# power_aug_25.net
KiCad netlist of a schematic drawn in EAGLE
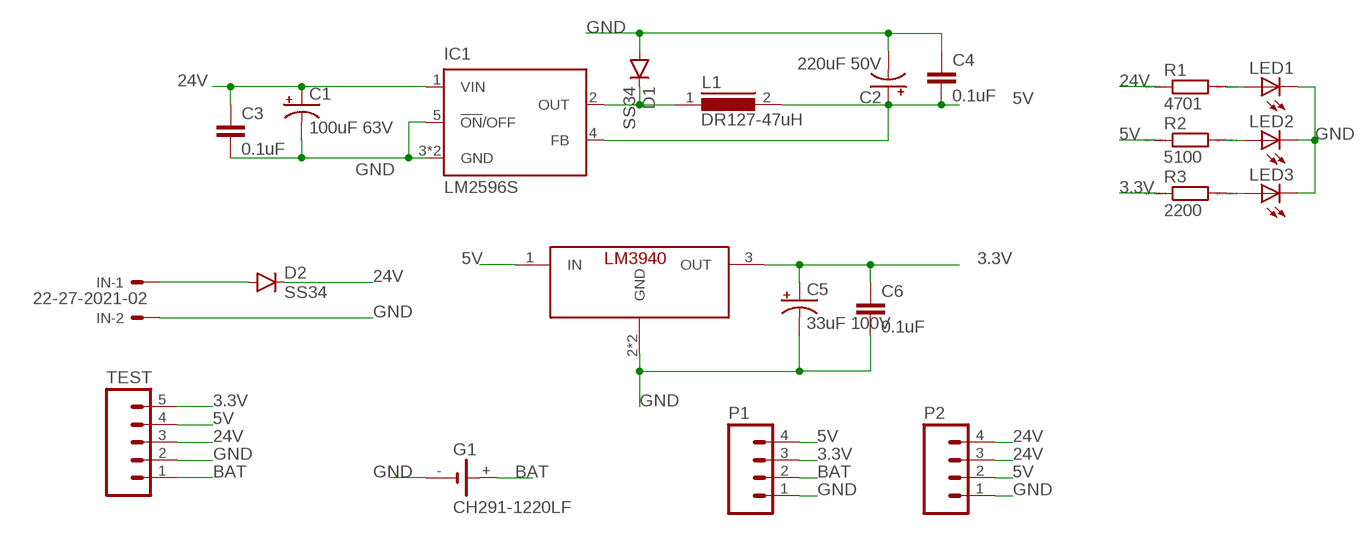
[diagram p0: schematic, sheet 1]

(export (version "E")
  (design (tool "Eeschema 10.0.6"))
  (components
    (comp (ref "C1")
      (value "100uF 63V")
      (footprint "eagle-import:NIC_10X10.5_CAP")
      (libsource (lib "eagle-import") (part "100UF-63V-20%(ELECT)"))
    )
    (comp (ref "C2")
      (value "220uF 50V")
      (footprint "eagle-import:NIC_10X10.5_CAP")
      (libsource (lib "eagle-import") (part "100UF-63V-20%(ELECT)"))
    )
    (comp (ref "C3")
      (value "0.1uF")
      (footprint "eagle-import:0603-CAP")
      (libsource (lib "eagle-import") (part "0.1UF-100V-10%(0603)"))
    )
    (comp (ref "C4")
      (value "0.1uF")
      (footprint "eagle-import:0603-CAP")
      (libsource (lib "eagle-import") (part "0.1UF-100V-10%(0603)"))
    )
    (comp (ref "C5")
      (value "33uF 100V")
      (footprint "eagle-import:NIC_10X10.5_CAP")
      (libsource (lib "eagle-import") (part "100UF-63V-20%(ELECT)"))
    )
    (comp (ref "C6")
      (value "0.1uF")
      (footprint "eagle-import:0603-CAP")
      (libsource (lib "eagle-import") (part "0.1UF-100V-10%(0603)"))
    )
    (comp (ref "D1")
      (value "SS34")
      (footprint "eagle-import:SMA-DIODE_ALT")
      (libsource (lib "eagle-import") (part "DIODESMA-ALT"))
    )
    (comp (ref "D2")
      (value "SS34")
      (footprint "eagle-import:SMA-DIODE_ALT")
      (libsource (lib "eagle-import") (part "DIODESMA-ALT"))
    )
    (comp (ref "G1")
      (value "CH291-1220LF")
      (footprint "eagle-import:CH291-1220LF")
      (libsource (lib "eagle-import") (part "CH291-1220LF"))
    )
    (comp (ref "IC1")
      (value "LM2596S")
      (footprint "eagle-import:TO263-5")
      (fields (field (name "MF") "NATIONAL SEMICONDUCTOR") (field (name "MPN") "LM2596S-ADJ/NOPB"))
      (libsource (lib "eagle-import") (part "LM2596S"))
    )
    (comp (ref "IN")
      (value "22-27-2021-02")
      (footprint "eagle-import:6410-02")
      (libsource (lib "eagle-import") (part "22-?-0227-2021"))
    )
    (comp (ref "L1")
      (value "DR127-47uH")
      (footprint "eagle-import:DR127")
      (libsource (lib "eagle-import") (part "DR127"))
    )
    (comp (ref "LED1")
      (value "LEDCHIPLED_0805")
      (footprint "eagle-import:CHIPLED_0805")
      (libsource (lib "eagle-import") (part "LEDCHIPLED_0805"))
    )
    (comp (ref "LED2")
      (value "LEDCHIPLED_0805")
      (footprint "eagle-import:CHIPLED_0805")
      (libsource (lib "eagle-import") (part "LEDCHIPLED_0805"))
    )
    (comp (ref "LED3")
      (value "LEDCHIPLED_0805")
      (footprint "eagle-import:CHIPLED_0805")
      (libsource (lib "eagle-import") (part "LEDCHIPLED_0805"))
    )
    (comp (ref "P1")
      (value "M04SMD2")
      (footprint "eagle-import:1X04-1MM-RA")
      (libsource (lib "eagle-import") (part "M04SMD2"))
    )
    (comp (ref "P2")
      (value "M04SMD2")
      (footprint "eagle-import:1X04-1MM-RA")
      (libsource (lib "eagle-import") (part "M04SMD2"))
    )
    (comp (ref "R1")
      (value "4701")
      (footprint "eagle-import:R0603")
      (libsource (lib "eagle-import") (part "RR0603"))
    )
    (comp (ref "R2")
      (value "5100")
      (footprint "eagle-import:R0603")
      (libsource (lib "eagle-import") (part "RR0603"))
    )
    (comp (ref "R3")
      (value "2200")
      (footprint "eagle-import:R0603")
      (libsource (lib "eagle-import") (part "RR0603"))
    )
    (comp (ref "TEST")
      (value "M05LOCK_LONGPADS")
      (footprint "eagle-import:1X05_LOCK_LONGPADS")
      (libsource (lib "eagle-import") (part "M05LOCK_LONGPADS"))
    )
    (comp (ref "U$1")
      (value "LM3940")
      (footprint "eagle-import:SOT223")
      (libsource (lib "eagle-import") (part "LM3940"))
    )
  )
  (nets
    (net (code "1") (name "/3.3V") (class "Default")
      (node (ref "C5") (pin "+") (pinfunction "+_+") (pintype "passive"))
      (node (ref "C6") (pin "1") (pinfunction "1_1") (pintype "passive"))
      (node (ref "P1") (pin "3") (pinfunction "3_3") (pintype "passive"))
      (node (ref "R3") (pin "1") (pinfunction "1_1") (pintype "passive"))
      (node (ref "TEST") (pin "5") (pinfunction "5_5") (pintype "passive"))
      (node (ref "U$1") (pin "3") (pinfunction "OUT_3") (pintype "bidirectional"))
    )
    (net (code "2") (name "/5V") (class "Default")
      (node (ref "C2") (pin "+") (pinfunction "+_+") (pintype "passive"))
      (node (ref "C4") (pin "2") (pinfunction "2_2") (pintype "passive"))
      (node (ref "IC1") (pin "4") (pinfunction "FB_4") (pintype "input"))
      (node (ref "L1") (pin "2") (pinfunction "2_2") (pintype "passive"))
      (node (ref "P1") (pin "4") (pinfunction "4_4") (pintype "passive"))
      (node (ref "P2") (pin "2") (pinfunction "2_2") (pintype "passive"))
      (node (ref "R2") (pin "1") (pinfunction "1_1") (pintype "passive"))
      (node (ref "TEST") (pin "4") (pinfunction "4_4") (pintype "passive"))
      (node (ref "U$1") (pin "1") (pinfunction "IN_1") (pintype "bidirectional"))
    )
    (net (code "3") (name "/24V") (class "Default")
      (node (ref "C1") (pin "+") (pinfunction "+_+") (pintype "passive"))
      (node (ref "C3") (pin "1") (pinfunction "1_1") (pintype "passive"))
      (node (ref "D2") (pin "C") (pinfunction "C_C") (pintype "passive"))
      (node (ref "IC1") (pin "1") (pinfunction "VIN_1") (pintype "input"))
      (node (ref "P2") (pin "3") (pinfunction "3_3") (pintype "passive"))
      (node (ref "P2") (pin "4") (pinfunction "4_4") (pintype "passive"))
      (node (ref "R1") (pin "1") (pinfunction "1_1") (pintype "passive"))
      (node (ref "TEST") (pin "3") (pinfunction "3_3") (pintype "passive"))
    )
    (net (code "4") (name "/BAT") (class "Default")
      (node (ref "G1") (pin "+") (pinfunction "+_+") (pintype "passive"))
      (node (ref "P1") (pin "2") (pinfunction "2_2") (pintype "passive"))
      (node (ref "TEST") (pin "1") (pinfunction "1_1") (pintype "passive"))
    )
    (net (code "5") (name "/GND") (class "Default")
      (node (ref "C1") (pin "-") (pinfunction "-_-") (pintype "passive"))
      (node (ref "C2") (pin "-") (pinfunction "-_-") (pintype "passive"))
      (node (ref "C3") (pin "2") (pinfunction "2_2") (pintype "passive"))
      (node (ref "C4") (pin "1") (pinfunction "1_1") (pintype "passive"))
      (node (ref "C5") (pin "-") (pinfunction "-_-") (pintype "passive"))
      (node (ref "C6") (pin "2") (pinfunction "2_2") (pintype "passive"))
      (node (ref "D1") (pin "A") (pinfunction "A_A") (pintype "passive"))
      (node (ref "G1") (pin "-") (pinfunction "-_-") (pintype "passive"))
      (node (ref "IC1") (pin "3") (pinfunction "GND_3") (pintype "power_in"))
      (node (ref "IC1") (pin "5") (pinfunction "~{ON}/OFF_5") (pintype "input"))
      (node (ref "IC1") (pin "6") (pinfunction "GND_6") (pintype "power_in"))
      (node (ref "IN") (pin "2") (pinfunction "S_2") (pintype "passive"))
      (node (ref "LED1") (pin "C") (pinfunction "C_C") (pintype "passive"))
      (node (ref "LED2") (pin "C") (pinfunction "C_C") (pintype "passive"))
      (node (ref "LED3") (pin "C") (pinfunction "C_C") (pintype "passive"))
      (node (ref "P1") (pin "1") (pinfunction "1_1") (pintype "passive"))
      (node (ref "P2") (pin "1") (pinfunction "1_1") (pintype "passive"))
      (node (ref "TEST") (pin "2") (pinfunction "2_2") (pintype "passive"))
      (node (ref "U$1") (pin "2") (pinfunction "GND_2") (pintype "bidirectional"))
      (node (ref "U$1") (pin "4") (pinfunction "GND_4") (pintype "bidirectional"))
    )
    (net (code "6") (name "Net-(IC1-OUT)") (class "Default")
      (node (ref "D1") (pin "C") (pinfunction "C_C") (pintype "passive"))
      (node (ref "IC1") (pin "2") (pinfunction "OUT_2") (pintype "output"))
      (node (ref "L1") (pin "1") (pinfunction "1_1") (pintype "passive"))
    )
    (net (code "7") (name "Net-(INA-S)") (class "Default")
      (node (ref "D2") (pin "A") (pinfunction "A_A") (pintype "passive"))
      (node (ref "IN") (pin "1") (pinfunction "S_1") (pintype "passive"))
    )
    (net (code "8") (name "Net-(LED1-PadA)") (class "Default")
      (node (ref "LED1") (pin "A") (pinfunction "A_A") (pintype "passive"))
      (node (ref "R1") (pin "2") (pinfunction "2_2") (pintype "passive"))
    )
    (net (code "9") (name "Net-(LED2-PadA)") (class "Default")
      (node (ref "LED2") (pin "A") (pinfunction "A_A") (pintype "passive"))
      (node (ref "R2") (pin "2") (pinfunction "2_2") (pintype "passive"))
    )
    (net (code "10") (name "Net-(LED3-PadA)") (class "Default")
      (node (ref "LED3") (pin "A") (pinfunction "A_A") (pintype "passive"))
      (node (ref "R3") (pin "2") (pinfunction "2_2") (pintype "passive"))
    )
  )
)
